# 8_Zyntra-Ethernet.net
KiCad netlist of a schematic drawn in Altium Designer
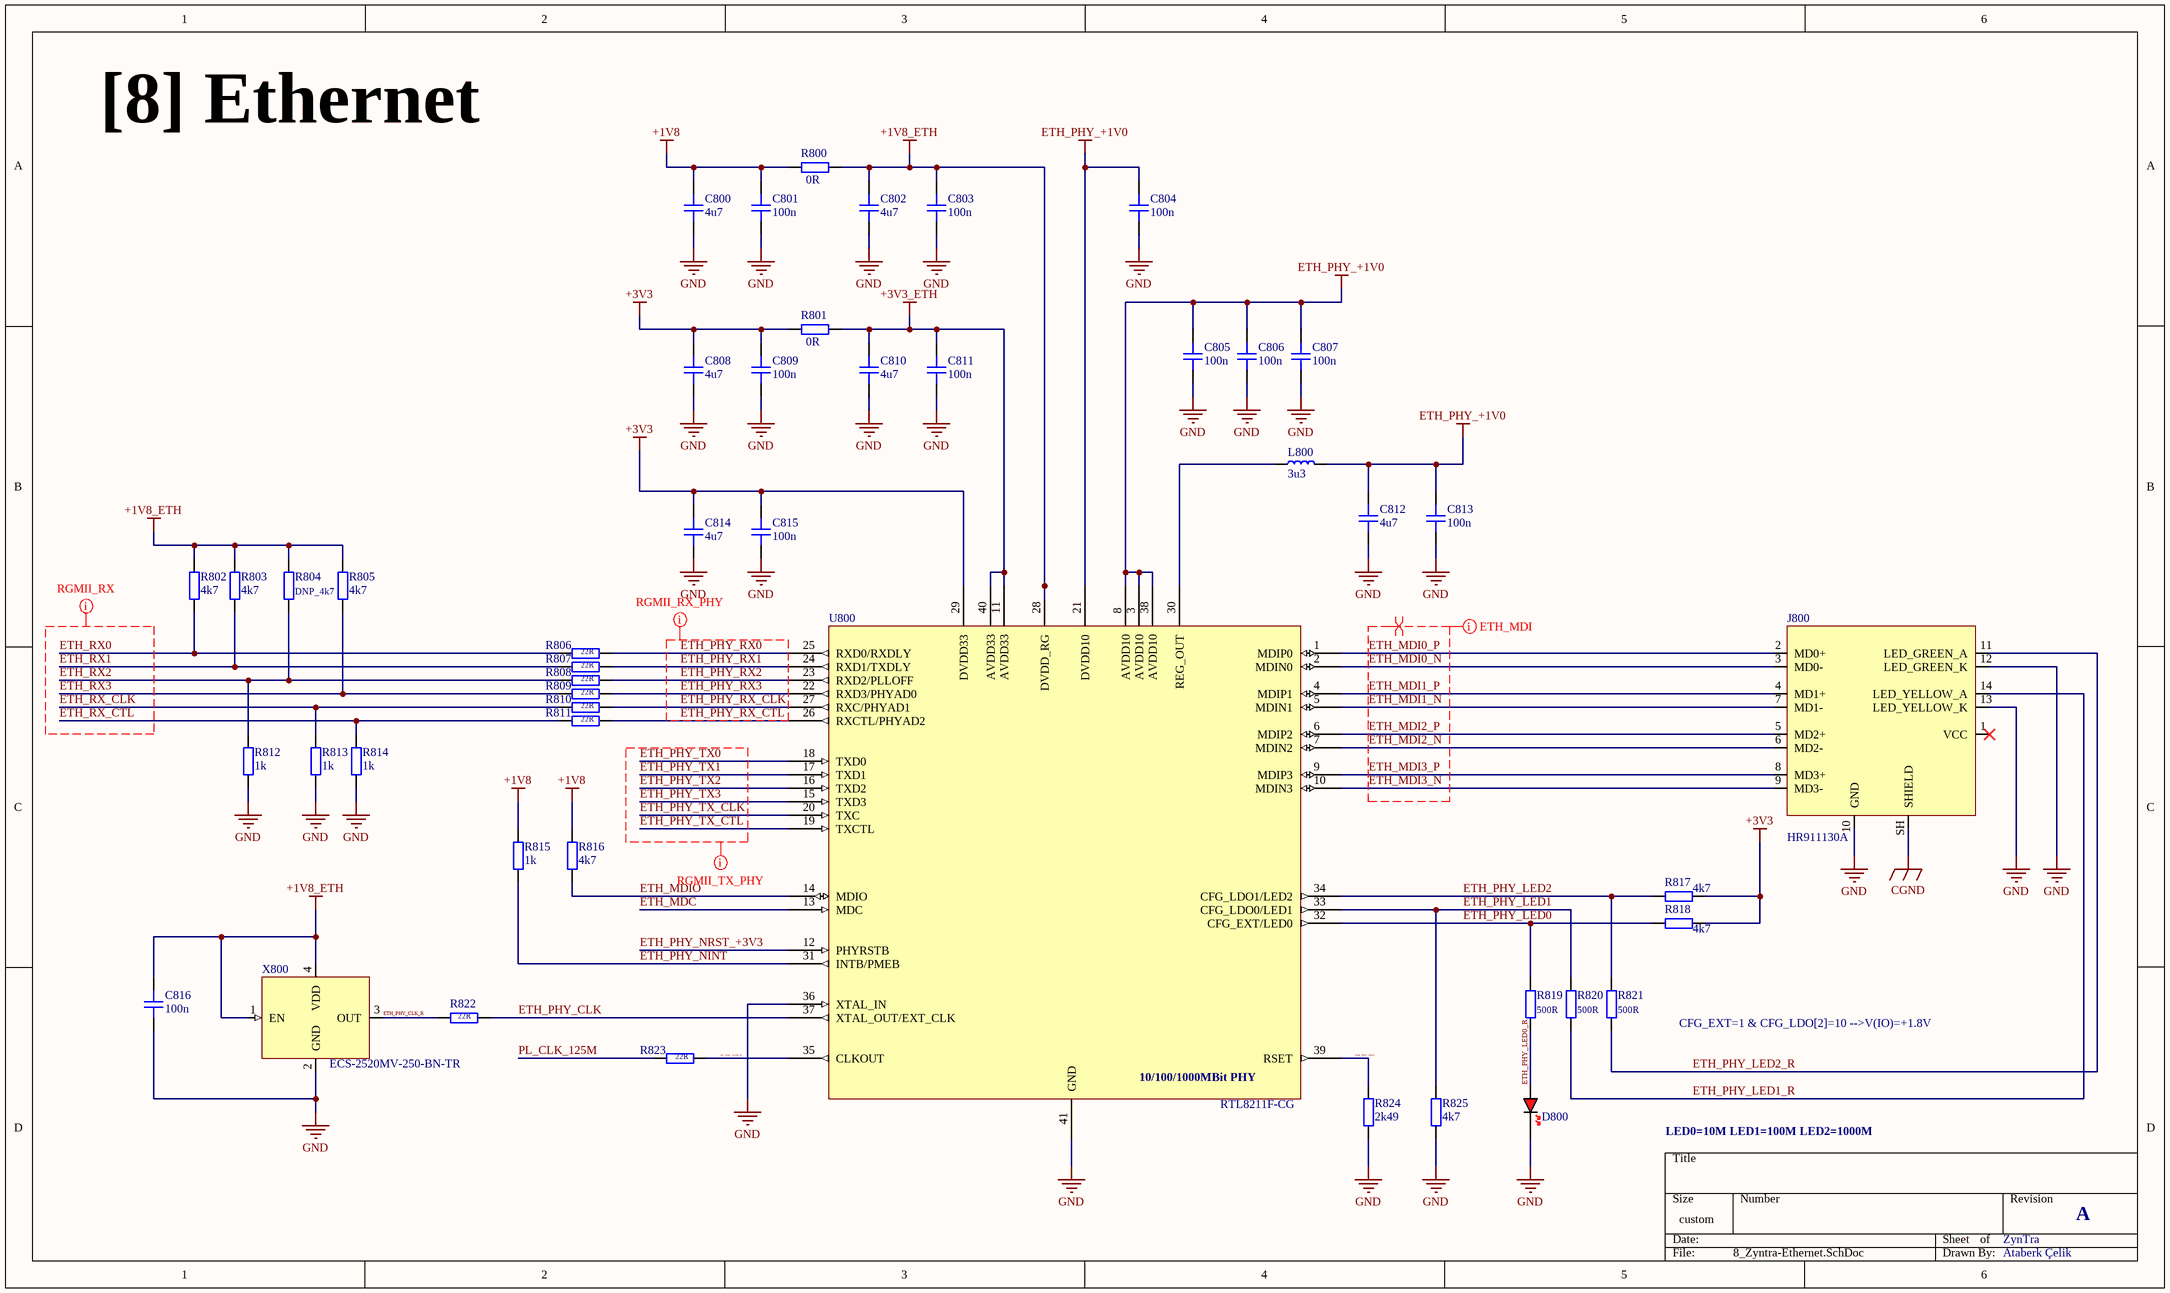
[diagram p0: 8_Zyntra-Ethernet.SchDoc]

(export (version "E")
  (design (tool "Eeschema 10.0.6"))
  (components
    (comp (ref "C800")
      (value "4u7")
      (footprint "CAP_0201")
      (description "Capacitor SMD 0201")
      (libsource (lib "Schematic-Lib-PhilsLab") (part "CAP_0201"))
    )
    (comp (ref "C801")
      (value "100n")
      (footprint "CAP_0201")
      (description "Capacitor SMD 0201")
      (libsource (lib "Schematic-Lib-PhilsLab") (part "CAP_0201"))
    )
    (comp (ref "C802")
      (value "4u7")
      (footprint "CAP_0201")
      (description "Capacitor SMD 0201")
      (libsource (lib "Schematic-Lib-PhilsLab") (part "CAP_0201"))
    )
    (comp (ref "C803")
      (value "100n")
      (footprint "CAP_0201")
      (description "Capacitor SMD 0201")
      (libsource (lib "Schematic-Lib-PhilsLab") (part "CAP_0201"))
    )
    (comp (ref "C804")
      (value "100n")
      (footprint "CAP_0201")
      (description "Capacitor SMD 0201")
      (libsource (lib "Schematic-Lib-PhilsLab") (part "CAP_0201"))
    )
    (comp (ref "C805")
      (value "100n")
      (footprint "CAP_0201")
      (description "Capacitor SMD 0201")
      (libsource (lib "Schematic-Lib-PhilsLab") (part "CAP_0201"))
    )
    (comp (ref "C806")
      (value "100n")
      (footprint "CAP_0201")
      (description "Capacitor SMD 0201")
      (libsource (lib "Schematic-Lib-PhilsLab") (part "CAP_0201"))
    )
    (comp (ref "C807")
      (value "100n")
      (footprint "CAP_0201")
      (description "Capacitor SMD 0201")
      (libsource (lib "Schematic-Lib-PhilsLab") (part "CAP_0201"))
    )
    (comp (ref "C808")
      (value "4u7")
      (footprint "CAP_0201")
      (description "Capacitor SMD 0201")
      (libsource (lib "Schematic-Lib-PhilsLab") (part "CAP_0201"))
    )
    (comp (ref "C809")
      (value "100n")
      (footprint "CAP_0201")
      (description "Capacitor SMD 0201")
      (libsource (lib "Schematic-Lib-PhilsLab") (part "CAP_0201"))
    )
    (comp (ref "C810")
      (value "4u7")
      (footprint "CAP_0201")
      (description "Capacitor SMD 0201")
      (libsource (lib "Schematic-Lib-PhilsLab") (part "CAP_0201"))
    )
    (comp (ref "C811")
      (value "100n")
      (footprint "CAP_0201")
      (description "Capacitor SMD 0201")
      (libsource (lib "Schematic-Lib-PhilsLab") (part "CAP_0201"))
    )
    (comp (ref "C812")
      (value "4u7")
      (footprint "CAP_0201")
      (description "Capacitor SMD 0201")
      (libsource (lib "Schematic-Lib-PhilsLab") (part "CAP_0201"))
    )
    (comp (ref "C813")
      (value "100n")
      (footprint "CAP_0201")
      (description "Capacitor SMD 0201")
      (libsource (lib "Schematic-Lib-PhilsLab") (part "CAP_0201"))
    )
    (comp (ref "C814")
      (value "4u7")
      (footprint "CAP_0201")
      (description "Capacitor SMD 0201")
      (libsource (lib "Schematic-Lib-PhilsLab") (part "CAP_0201"))
    )
    (comp (ref "C815")
      (value "100n")
      (footprint "CAP_0201")
      (description "Capacitor SMD 0201")
      (libsource (lib "Schematic-Lib-PhilsLab") (part "CAP_0201"))
    )
    (comp (ref "C816")
      (value "100n")
      (footprint "CAP_0201")
      (description "Capacitor SMD 0201")
      (libsource (lib "Schematic-Lib-PhilsLab") (part "CAP_0201"))
    )
    (comp (ref "D800")
      (value "RED")
      (footprint "LED_0603_RED")
      (description "LED 0603 RED SMD")
      (libsource (lib "Schematic-Lib-PhilsLab") (part "LED_0603_RED"))
    )
    (comp (ref "J800")
      (value "HR911130A")
      (footprint "HR911130A")
      (description "100/1000Base-T Magnetics Single-Port RJ45 Connector with Integrated Magnetics and LEDs")
      (fields (field (name "MANUFACTURER") "Hanrun"))
      (libsource (lib "Schematic-Lib-PhilsLab") (part "HR911130A"))
    )
    (comp (ref "L800")
      (value "3u3")
      (footprint "IND_0603")
      (description "Inductor SMD 0603")
      (libsource (lib "Schematic-Lib-PhilsLab") (part "IND_0603"))
    )
    (comp (ref "R800")
      (value "0R")
      (footprint "RES_0402")
      (description "Resistor SMD 0402")
      (libsource (lib "Schematic-Lib-PhilsLab") (part "RES_0402"))
    )
    (comp (ref "R801")
      (value "0R")
      (footprint "RES_0402")
      (description "Resistor SMD 0402")
      (libsource (lib "Schematic-Lib-PhilsLab") (part "RES_0402"))
    )
    (comp (ref "R802")
      (value "4k7")
      (footprint "RES_0402")
      (description "Resistor SMD 0402")
      (libsource (lib "Schematic-Lib-PhilsLab") (part "RES_0402"))
    )
    (comp (ref "R803")
      (value "4k7")
      (footprint "RES_0402")
      (description "Resistor SMD 0402")
      (libsource (lib "Schematic-Lib-PhilsLab") (part "RES_0402"))
    )
    (comp (ref "R804")
      (value "DNP_4k7")
      (footprint "RES_0402")
      (description "Resistor SMD 0402")
      (libsource (lib "Schematic-Lib-PhilsLab") (part "RES_0402"))
    )
    (comp (ref "R805")
      (value "4k7")
      (footprint "RES_0402")
      (description "Resistor SMD 0402")
      (libsource (lib "Schematic-Lib-PhilsLab") (part "RES_0402"))
    )
    (comp (ref "R806")
      (value "22R")
      (footprint "RES_0402")
      (description "Resistor SMD 0402")
      (libsource (lib "Schematic-Lib-PhilsLab") (part "RES_0402"))
    )
    (comp (ref "R807")
      (value "22R")
      (footprint "RES_0402")
      (description "Resistor SMD 0402")
      (libsource (lib "Schematic-Lib-PhilsLab") (part "RES_0402"))
    )
    (comp (ref "R808")
      (value "22R")
      (footprint "RES_0402")
      (description "Resistor SMD 0402")
      (libsource (lib "Schematic-Lib-PhilsLab") (part "RES_0402"))
    )
    (comp (ref "R809")
      (value "22R")
      (footprint "RES_0402")
      (description "Resistor SMD 0402")
      (libsource (lib "Schematic-Lib-PhilsLab") (part "RES_0402"))
    )
    (comp (ref "R810")
      (value "22R")
      (footprint "RES_0402")
      (description "Resistor SMD 0402")
      (libsource (lib "Schematic-Lib-PhilsLab") (part "RES_0402"))
    )
    (comp (ref "R811")
      (value "22R")
      (footprint "RES_0402")
      (description "Resistor SMD 0402")
      (libsource (lib "Schematic-Lib-PhilsLab") (part "RES_0402"))
    )
    (comp (ref "R812")
      (value "1k")
      (footprint "RES_0402")
      (description "Resistor SMD 0402")
      (libsource (lib "Schematic-Lib-PhilsLab") (part "RES_0402"))
    )
    (comp (ref "R813")
      (value "1k")
      (footprint "RES_0402")
      (description "Resistor SMD 0402")
      (libsource (lib "Schematic-Lib-PhilsLab") (part "RES_0402"))
    )
    (comp (ref "R814")
      (value "1k")
      (footprint "RES_0402")
      (description "Resistor SMD 0402")
      (libsource (lib "Schematic-Lib-PhilsLab") (part "RES_0402"))
    )
    (comp (ref "R815")
      (value "1k")
      (footprint "RES_0402")
      (description "Resistor SMD 0402")
      (libsource (lib "Schematic-Lib-PhilsLab") (part "RES_0402"))
    )
    (comp (ref "R816")
      (value "4k7")
      (footprint "RES_0402")
      (description "Resistor SMD 0402")
      (libsource (lib "Schematic-Lib-PhilsLab") (part "RES_0402"))
    )
    (comp (ref "R817")
      (value "4k7")
      (footprint "RES_0402")
      (description "Resistor SMD 0402")
      (libsource (lib "Schematic-Lib-PhilsLab") (part "RES_0402"))
    )
    (comp (ref "R818")
      (value "4k7")
      (footprint "RES_0402")
      (description "Resistor SMD 0402")
      (libsource (lib "Schematic-Lib-PhilsLab") (part "RES_0402"))
    )
    (comp (ref "R819")
      (value "500R")
      (footprint "RES_0402")
      (description "Resistor SMD 0402")
      (libsource (lib "Schematic-Lib-PhilsLab") (part "RES_0402"))
    )
    (comp (ref "R820")
      (value "500R")
      (footprint "RES_0402")
      (description "Resistor SMD 0402")
      (libsource (lib "Schematic-Lib-PhilsLab") (part "RES_0402"))
    )
    (comp (ref "R821")
      (value "500R")
      (footprint "RES_0402")
      (description "Resistor SMD 0402")
      (libsource (lib "Schematic-Lib-PhilsLab") (part "RES_0402"))
    )
    (comp (ref "R822")
      (value "22R")
      (footprint "RES_0402")
      (description "Resistor SMD 0402")
      (libsource (lib "Schematic-Lib-PhilsLab") (part "RES_0402"))
    )
    (comp (ref "R823")
      (value "22R")
      (footprint "RES_0402")
      (description "Resistor SMD 0402")
      (libsource (lib "Schematic-Lib-PhilsLab") (part "RES_0402"))
    )
    (comp (ref "R824")
      (value "2k49")
      (footprint "RES_0402")
      (description "Resistor SMD 0402")
      (libsource (lib "Schematic-Lib-PhilsLab") (part "RES_0402"))
    )
    (comp (ref "R825")
      (value "4k7")
      (footprint "RES_0402")
      (description "Resistor SMD 0402")
      (libsource (lib "Schematic-Lib-PhilsLab") (part "RES_0402"))
    )
    (comp (ref "U800")
      (value "RTL8211F-CG")
      (footprint "QFN40, 5x5mm")
      (description "INTEGRATED 10/100/1000M ETHERNET\r\nPRECISION TRANSCEIVER")
      (fields (field (name "MANUFACTURER") "REALTEK"))
      (libsource (lib "AtaSchLib") (part "RTL8211F-CG"))
    )
    (comp (ref "X800")
      (value "ECS-2520MV-250-BN-TR")
      (footprint "XTAL_2520")
      (fields
        (field (name "MANUFACTURER") "ECS")
        (field (name "MANUFACTURER PART NUMBER") "ECS-2520MV-130-BN-TR")
      )
      (libsource (lib "Schematic-Lib-PhilsLab") (part "ECS-2520MV-130-BN-TR"))
    )
  )
  (nets
    (net (code "1") (name "+1V8") (class "Default")
      (node (ref "C800") (pin "2") (pinfunction "2_2") (pintype "passive"))
      (node (ref "C801") (pin "2") (pinfunction "2_2") (pintype "passive"))
      (node (ref "R800") (pin "1") (pinfunction "1_1") (pintype "passive"))
      (node (ref "R815") (pin "2") (pinfunction "2_2") (pintype "passive"))
      (node (ref "R816") (pin "2") (pinfunction "2_2") (pintype "passive"))
    )
    (net (code "2") (name "+1V8_ETH") (class "Default")
      (node (ref "C802") (pin "2") (pinfunction "2_2") (pintype "passive"))
      (node (ref "C803") (pin "2") (pinfunction "2_2") (pintype "passive"))
      (node (ref "C816") (pin "2") (pinfunction "2_2") (pintype "passive"))
      (node (ref "R800") (pin "2") (pinfunction "2_2") (pintype "passive"))
      (node (ref "R802") (pin "2") (pinfunction "2_2") (pintype "passive"))
      (node (ref "R803") (pin "2") (pinfunction "2_2") (pintype "passive"))
      (node (ref "R804") (pin "2") (pinfunction "2_2") (pintype "passive"))
      (node (ref "R805") (pin "2") (pinfunction "2_2") (pintype "passive"))
      (node (ref "U800") (pin "28") (pinfunction "DVDD_RG_28") (pintype "power_in"))
      (node (ref "X800") (pin "1") (pinfunction "EN_1") (pintype "input"))
      (node (ref "X800") (pin "4") (pinfunction "VDD_4") (pintype "power_in"))
    )
    (net (code "3") (name "+3V3") (class "Default")
      (node (ref "C808") (pin "2") (pinfunction "2_2") (pintype "passive"))
      (node (ref "C809") (pin "2") (pinfunction "2_2") (pintype "passive"))
      (node (ref "C814") (pin "2") (pinfunction "2_2") (pintype "passive"))
      (node (ref "C815") (pin "2") (pinfunction "2_2") (pintype "passive"))
      (node (ref "R801") (pin "1") (pinfunction "1_1") (pintype "passive"))
      (node (ref "R817") (pin "2") (pinfunction "2_2") (pintype "passive"))
      (node (ref "R818") (pin "2") (pinfunction "2_2") (pintype "passive"))
      (node (ref "U800") (pin "29") (pinfunction "DVDD33_29") (pintype "power_in"))
    )
    (net (code "4") (name "+3V3_ETH") (class "Default")
      (node (ref "C810") (pin "2") (pinfunction "2_2") (pintype "passive"))
      (node (ref "C811") (pin "2") (pinfunction "2_2") (pintype "passive"))
      (node (ref "R801") (pin "2") (pinfunction "2_2") (pintype "passive"))
      (node (ref "U800") (pin "11") (pinfunction "AVDD33_11") (pintype "power_in"))
      (node (ref "U800") (pin "40") (pinfunction "AVDD33_40") (pintype "power_in"))
    )
    (net (code "5") (name "/ETH_MDC") (class "Default")
      (node (ref "U800") (pin "13") (pinfunction "MDC_13") (pintype "input"))
    )
    (net (code "6") (name "/ETH_MDI0_N") (class "Default")
      (node (ref "J800") (pin "3") (pinfunction "MD0-_3") (pintype "passive"))
      (node (ref "U800") (pin "2") (pinfunction "MDIN0_2") (pintype "bidirectional"))
    )
    (net (code "7") (name "/ETH_MDI0_P") (class "Default")
      (node (ref "J800") (pin "2") (pinfunction "MD0+_2") (pintype "passive"))
      (node (ref "U800") (pin "1") (pinfunction "MDIP0_1") (pintype "bidirectional"))
    )
    (net (code "8") (name "/ETH_MDI1_N") (class "Default")
      (node (ref "J800") (pin "7") (pinfunction "MD1-_7") (pintype "passive"))
      (node (ref "U800") (pin "5") (pinfunction "MDIN1_5") (pintype "bidirectional"))
    )
    (net (code "9") (name "/ETH_MDI1_P") (class "Default")
      (node (ref "J800") (pin "4") (pinfunction "MD1+_4") (pintype "passive"))
      (node (ref "U800") (pin "4") (pinfunction "MDIP1_4") (pintype "bidirectional"))
    )
    (net (code "10") (name "/ETH_MDI2_N") (class "Default")
      (node (ref "J800") (pin "6") (pinfunction "MD2-_6") (pintype "passive"))
      (node (ref "U800") (pin "7") (pinfunction "MDIN2_7") (pintype "bidirectional"))
    )
    (net (code "11") (name "/ETH_MDI2_P") (class "Default")
      (node (ref "J800") (pin "5") (pinfunction "MD2+_5") (pintype "passive"))
      (node (ref "U800") (pin "6") (pinfunction "MDIP2_6") (pintype "bidirectional"))
    )
    (net (code "12") (name "/ETH_MDI3_N") (class "Default")
      (node (ref "J800") (pin "9") (pinfunction "MD3-_9") (pintype "passive"))
      (node (ref "U800") (pin "10") (pinfunction "MDIN3_10") (pintype "bidirectional"))
    )
    (net (code "13") (name "/ETH_MDI3_P") (class "Default")
      (node (ref "J800") (pin "8") (pinfunction "MD3+_8") (pintype "passive"))
      (node (ref "U800") (pin "9") (pinfunction "MDIP3_9") (pintype "bidirectional"))
    )
    (net (code "14") (name "/ETH_MDIO") (class "Default")
      (node (ref "R816") (pin "1") (pinfunction "1_1") (pintype "passive"))
      (node (ref "U800") (pin "14") (pinfunction "MDIO_14") (pintype "bidirectional"))
    )
    (net (code "15") (name "/ETH_PHY_CLK") (class "Default")
      (node (ref "R822") (pin "1") (pinfunction "1_1") (pintype "passive"))
      (node (ref "U800") (pin "37") (pinfunction "XTAL_OUT/EXT_CLK_37") (pintype "output"))
    )
    (net (code "16") (name "/ETH_PHY_CLK_R") (class "Default")
      (node (ref "R822") (pin "2") (pinfunction "2_2") (pintype "passive"))
      (node (ref "X800") (pin "3") (pinfunction "OUT_3") (pintype "passive"))
    )
    (net (code "17") (name "/ETH_PHY_LED0") (class "Default")
      (node (ref "R818") (pin "1") (pinfunction "1_1") (pintype "passive"))
      (node (ref "R819") (pin "1") (pinfunction "1_1") (pintype "passive"))
      (node (ref "U800") (pin "32") (pinfunction "CFG_EXT/LED0_32") (pintype "output"))
    )
    (net (code "18") (name "/ETH_PHY_LED0_R") (class "Default")
      (node (ref "D800") (pin "A") (pinfunction "A_A") (pintype "passive"))
      (node (ref "R819") (pin "2") (pinfunction "2_2") (pintype "passive"))
    )
    (net (code "19") (name "/ETH_PHY_LED1") (class "Default")
      (node (ref "R820") (pin "1") (pinfunction "1_1") (pintype "passive"))
      (node (ref "R825") (pin "2") (pinfunction "2_2") (pintype "passive"))
      (node (ref "U800") (pin "33") (pinfunction "CFG_LDO0/LED1_33") (pintype "output"))
    )
    (net (code "20") (name "/ETH_PHY_LED1_R") (class "Default")
      (node (ref "J800") (pin "14") (pinfunction "LED_YELLOW_A_14") (pintype "passive"))
      (node (ref "R820") (pin "2") (pinfunction "2_2") (pintype "passive"))
    )
    (net (code "21") (name "/ETH_PHY_LED2") (class "Default")
      (node (ref "R817") (pin "1") (pinfunction "1_1") (pintype "passive"))
      (node (ref "R821") (pin "1") (pinfunction "1_1") (pintype "passive"))
      (node (ref "U800") (pin "34") (pinfunction "CFG_LDO1/LED2_34") (pintype "output"))
    )
    (net (code "22") (name "/ETH_PHY_LED2_R") (class "Default")
      (node (ref "J800") (pin "11") (pinfunction "LED_GREEN_A_11") (pintype "passive"))
      (node (ref "R821") (pin "2") (pinfunction "2_2") (pintype "passive"))
    )
    (net (code "23") (name "/ETH_PHY_NINT") (class "Default")
      (node (ref "R815") (pin "1") (pinfunction "1_1") (pintype "passive"))
      (node (ref "U800") (pin "31") (pinfunction "INTB/PMEB_31") (pintype "output"))
    )
    (net (code "24") (name "/ETH_PHY_NRST_+3V3") (class "Default")
      (node (ref "U800") (pin "12") (pinfunction "PHYRSTB_12") (pintype "input"))
    )
    (net (code "25") (name "/ETH_PHY_RSET") (class "Default")
      (node (ref "R824") (pin "1") (pinfunction "1_1") (pintype "passive"))
      (node (ref "U800") (pin "39") (pinfunction "RSET_39") (pintype "output"))
    )
    (net (code "26") (name "/ETH_PHY_RX0") (class "Default")
      (node (ref "R806") (pin "1") (pinfunction "1_1") (pintype "passive"))
      (node (ref "U800") (pin "25") (pinfunction "RXD0/RXDLY_25") (pintype "output"))
    )
    (net (code "27") (name "/ETH_PHY_RX1") (class "Default")
      (node (ref "R807") (pin "1") (pinfunction "1_1") (pintype "passive"))
      (node (ref "U800") (pin "24") (pinfunction "RXD1/TXDLY_24") (pintype "output"))
    )
    (net (code "28") (name "/ETH_PHY_RX2") (class "Default")
      (node (ref "R808") (pin "1") (pinfunction "1_1") (pintype "passive"))
      (node (ref "U800") (pin "23") (pinfunction "RXD2/PLLOFF_23") (pintype "output"))
    )
    (net (code "29") (name "/ETH_PHY_RX3") (class "Default")
      (node (ref "R809") (pin "1") (pinfunction "1_1") (pintype "passive"))
      (node (ref "U800") (pin "22") (pinfunction "RXD3/PHYAD0_22") (pintype "output"))
    )
    (net (code "30") (name "/ETH_PHY_RX_CLK") (class "Default")
      (node (ref "R810") (pin "1") (pinfunction "1_1") (pintype "passive"))
      (node (ref "U800") (pin "27") (pinfunction "RXC/PHYAD1_27") (pintype "output"))
    )
    (net (code "31") (name "/ETH_PHY_RX_CTL") (class "Default")
      (node (ref "R811") (pin "1") (pinfunction "1_1") (pintype "passive"))
      (node (ref "U800") (pin "26") (pinfunction "RXCTL/PHYAD2_26") (pintype "output"))
    )
    (net (code "32") (name "/ETH_PHY_TX0") (class "Default")
      (node (ref "U800") (pin "18") (pinfunction "TXD0_18") (pintype "input"))
    )
    (net (code "33") (name "/ETH_PHY_TX1") (class "Default")
      (node (ref "U800") (pin "17") (pinfunction "TXD1_17") (pintype "input"))
    )
    (net (code "34") (name "/ETH_PHY_TX2") (class "Default")
      (node (ref "U800") (pin "16") (pinfunction "TXD2_16") (pintype "input"))
    )
    (net (code "35") (name "/ETH_PHY_TX3") (class "Default")
      (node (ref "U800") (pin "15") (pinfunction "TXD3_15") (pintype "input"))
    )
    (net (code "36") (name "/ETH_PHY_TX_CLK") (class "Default")
      (node (ref "U800") (pin "20") (pinfunction "TXC_20") (pintype "input"))
    )
    (net (code "37") (name "/ETH_PHY_TX_CTL") (class "Default")
      (node (ref "U800") (pin "19") (pinfunction "TXCTL_19") (pintype "input"))
    )
    (net (code "38") (name "/ETH_RX0") (class "Default")
      (node (ref "R802") (pin "1") (pinfunction "1_1") (pintype "passive"))
      (node (ref "R806") (pin "2") (pinfunction "2_2") (pintype "passive"))
    )
    (net (code "39") (name "/ETH_RX1") (class "Default")
      (node (ref "R803") (pin "1") (pinfunction "1_1") (pintype "passive"))
      (node (ref "R807") (pin "2") (pinfunction "2_2") (pintype "passive"))
    )
    (net (code "40") (name "/ETH_RX2") (class "Default")
      (node (ref "R804") (pin "1") (pinfunction "1_1") (pintype "passive"))
      (node (ref "R808") (pin "2") (pinfunction "2_2") (pintype "passive"))
      (node (ref "R812") (pin "2") (pinfunction "2_2") (pintype "passive"))
    )
    (net (code "41") (name "/ETH_RX3") (class "Default")
      (node (ref "R805") (pin "1") (pinfunction "1_1") (pintype "passive"))
      (node (ref "R809") (pin "2") (pinfunction "2_2") (pintype "passive"))
    )
    (net (code "42") (name "/ETH_RX_CLK") (class "Default")
      (node (ref "R810") (pin "2") (pinfunction "2_2") (pintype "passive"))
      (node (ref "R813") (pin "2") (pinfunction "2_2") (pintype "passive"))
    )
    (net (code "43") (name "/ETH_RX_CTL") (class "Default")
      (node (ref "R811") (pin "2") (pinfunction "2_2") (pintype "passive"))
      (node (ref "R814") (pin "2") (pinfunction "2_2") (pintype "passive"))
    )
    (net (code "44") (name "/PL_CLK_125M") (class "Default")
      (node (ref "R823") (pin "2") (pinfunction "2_2") (pintype "passive"))
    )
    (net (code "45") (name "/PL_CLK_125M_R") (class "Default")
      (node (ref "R823") (pin "1") (pinfunction "1_1") (pintype "passive"))
      (node (ref "U800") (pin "35") (pinfunction "CLKOUT_35") (pintype "output"))
    )
    (net (code "46") (name "CGND") (class "Default")
      (node (ref "J800") (pin "SH") (pinfunction "SHIELD_SH") (pintype "passive"))
    )
    (net (code "47") (name "ETH_PHY_+1V0") (class "Default")
      (node (ref "C804") (pin "2") (pinfunction "2_2") (pintype "passive"))
      (node (ref "C805") (pin "2") (pinfunction "2_2") (pintype "passive"))
      (node (ref "C806") (pin "2") (pinfunction "2_2") (pintype "passive"))
      (node (ref "C807") (pin "2") (pinfunction "2_2") (pintype "passive"))
      (node (ref "C812") (pin "2") (pinfunction "2_2") (pintype "passive"))
      (node (ref "C813") (pin "2") (pinfunction "2_2") (pintype "passive"))
      (node (ref "L800") (pin "2") (pinfunction "2_2") (pintype "passive"))
      (node (ref "U800") (pin "21") (pinfunction "DVDD10_21") (pintype "power_in"))
      (node (ref "U800") (pin "3") (pinfunction "AVDD10_3") (pintype "power_in"))
      (node (ref "U800") (pin "38") (pinfunction "AVDD10_38") (pintype "power_in"))
      (node (ref "U800") (pin "8") (pinfunction "AVDD10_8") (pintype "power_in"))
    )
    (net (code "48") (name "GND") (class "Default")
      (node (ref "C800") (pin "1") (pinfunction "1_1") (pintype "passive"))
      (node (ref "C801") (pin "1") (pinfunction "1_1") (pintype "passive"))
      (node (ref "C802") (pin "1") (pinfunction "1_1") (pintype "passive"))
      (node (ref "C803") (pin "1") (pinfunction "1_1") (pintype "passive"))
      (node (ref "C804") (pin "1") (pinfunction "1_1") (pintype "passive"))
      (node (ref "C805") (pin "1") (pinfunction "1_1") (pintype "passive"))
      (node (ref "C806") (pin "1") (pinfunction "1_1") (pintype "passive"))
      (node (ref "C807") (pin "1") (pinfunction "1_1") (pintype "passive"))
      (node (ref "C808") (pin "1") (pinfunction "1_1") (pintype "passive"))
      (node (ref "C809") (pin "1") (pinfunction "1_1") (pintype "passive"))
      (node (ref "C810") (pin "1") (pinfunction "1_1") (pintype "passive"))
      (node (ref "C811") (pin "1") (pinfunction "1_1") (pintype "passive"))
      (node (ref "C812") (pin "1") (pinfunction "1_1") (pintype "passive"))
      (node (ref "C813") (pin "1") (pinfunction "1_1") (pintype "passive"))
      (node (ref "C814") (pin "1") (pinfunction "1_1") (pintype "passive"))
      (node (ref "C815") (pin "1") (pinfunction "1_1") (pintype "passive"))
      (node (ref "C816") (pin "1") (pinfunction "1_1") (pintype "passive"))
      (node (ref "D800") (pin "K") (pinfunction "K_K") (pintype "passive"))
      (node (ref "J800") (pin "10") (pinfunction "GND_10") (pintype "passive"))
      (node (ref "J800") (pin "12") (pinfunction "LED_GREEN_K_12") (pintype "passive"))
      (node (ref "J800") (pin "13") (pinfunction "LED_YELLOW_K_13") (pintype "passive"))
      (node (ref "R812") (pin "1") (pinfunction "1_1") (pintype "passive"))
      (node (ref "R813") (pin "1") (pinfunction "1_1") (pintype "passive"))
      (node (ref "R814") (pin "1") (pinfunction "1_1") (pintype "passive"))
      (node (ref "R824") (pin "2") (pinfunction "2_2") (pintype "passive"))
      (node (ref "R825") (pin "1") (pinfunction "1_1") (pintype "passive"))
      (node (ref "U800") (pin "36") (pinfunction "XTAL_IN_36") (pintype "input"))
      (node (ref "U800") (pin "41") (pinfunction "GND_41") (pintype "power_in"))
      (node (ref "X800") (pin "2") (pinfunction "GND_2") (pintype "power_in"))
    )
    (net (code "49") (name "Net-(U800-REG_OUT)") (class "Default")
      (node (ref "L800") (pin "1") (pinfunction "1_1") (pintype "passive"))
      (node (ref "U800") (pin "30") (pinfunction "REG_OUT_30") (pintype "power_in"))
    )
    (net (code "50") (name "unconnected-(J800-VCC-Pad1)") (class "Default")
      (node (ref "J800") (pin "1") (pinfunction "VCC_1") (pintype "passive+no_connect"))
    )
  )
)
